# IR_Transmitter.net
KiCad netlist of a schematic drawn in Altium Designer
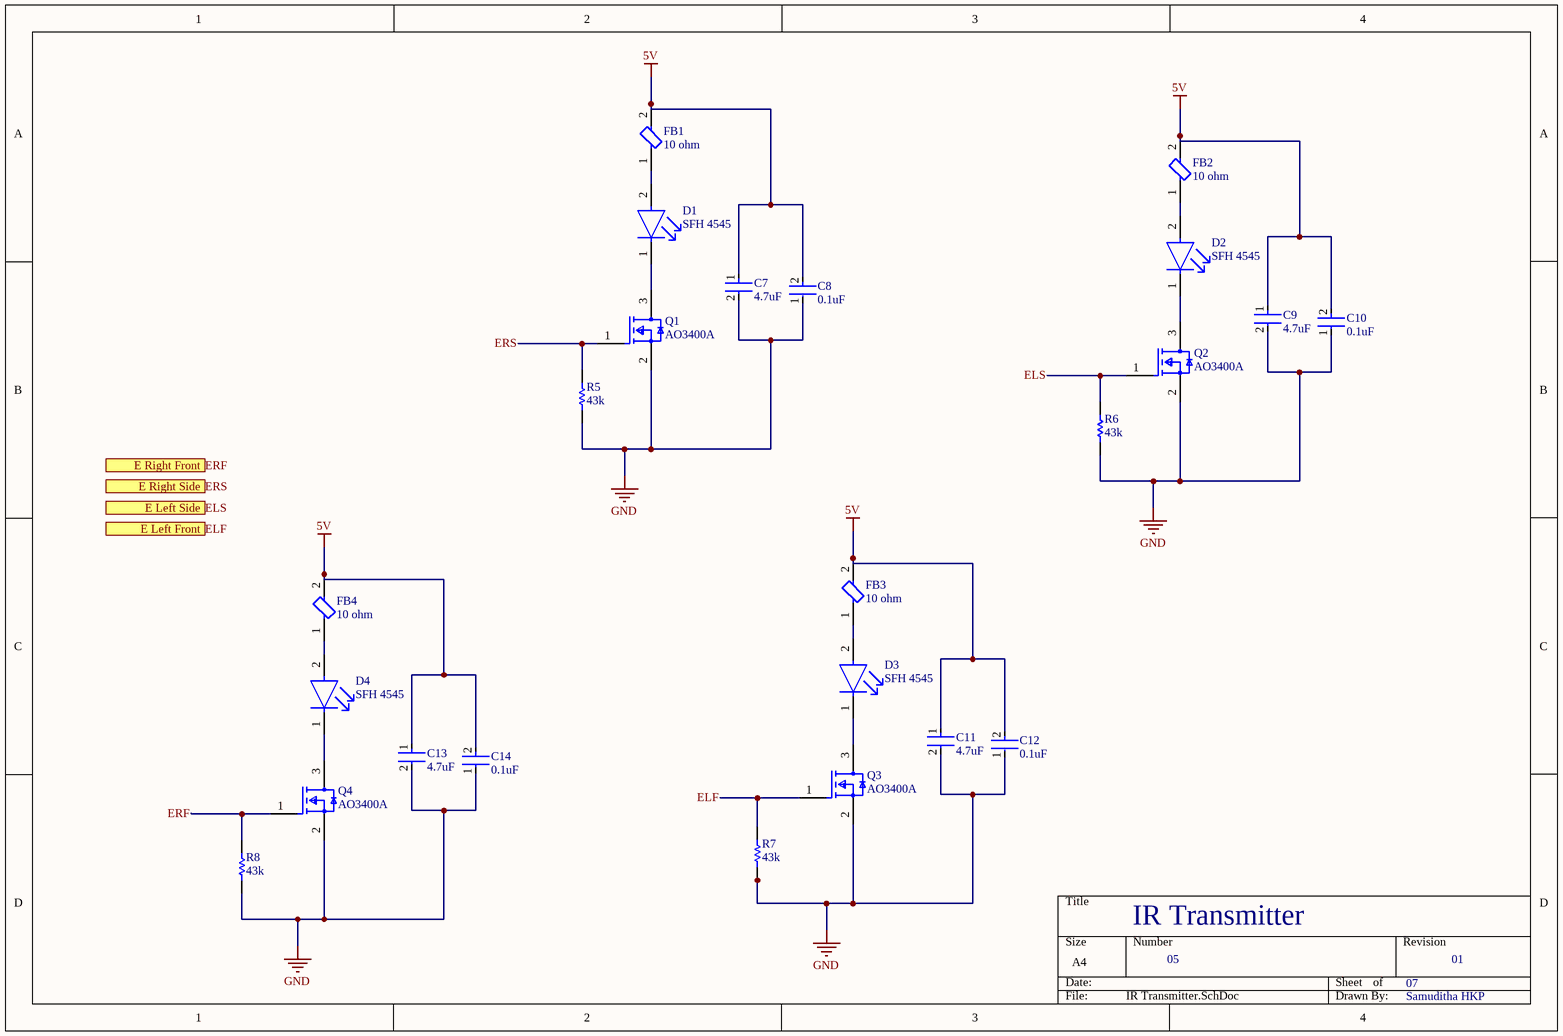
[diagram p0: IR Transmitter.SchDoc]

(export (version "E")
  (design (tool "Eeschema 10.0.6"))
  (components
    (comp (ref "C7")
      (value "4.7uF")
      (footprint "FP-GRM155-0_1-IPC_B")
      (description "Chip Multilayer Ceramic Capacitors for General Purpose, 0402, 4.7uF, X5R, 15%, 20%, 6.3V")
      (fields (field (name "VOLTAGE") "6.3V") (field (name "TOLERANCE") "20%"))
      (libsource (lib "Altium Content Vault") (part "11868f565c42a9108669ba33697ecf6"))
    )
    (comp (ref "C8")
      (value "0.1uF")
      (footprint "FP-GRM15-MFG")
      (description "CAP CER 0.1UF 16V X7R 0402")
      (fields (field (name "MANUFACTURER PART NUMBER") "GRM155R71C104KA88D") (field (name "TOLERANCE") "10%"))
      (libsource (lib "Altium Content Vault") (part "236180d848d6139a670b325ea6854c9"))
    )
    (comp (ref "C9")
      (value "4.7uF")
      (footprint "FP-GRM155-0_1-IPC_B")
      (description "Chip Multilayer Ceramic Capacitors for General Purpose, 0402, 4.7uF, X5R, 15%, 20%, 6.3V")
      (fields (field (name "VOLTAGE") "6.3V") (field (name "TOLERANCE") "20%"))
      (libsource (lib "Altium Content Vault") (part "11868f565c42a9108669ba33697ecf6"))
    )
    (comp (ref "C10")
      (value "0.1uF")
      (footprint "FP-GRM15-MFG")
      (description "CAP CER 0.1UF 16V X7R 0402")
      (fields (field (name "MANUFACTURER PART NUMBER") "GRM155R71C104KA88D") (field (name "TOLERANCE") "10%"))
      (libsource (lib "Altium Content Vault") (part "236180d848d6139a670b325ea6854c9"))
    )
    (comp (ref "C11")
      (value "4.7uF")
      (footprint "FP-GRM155-0_1-IPC_B")
      (description "Chip Multilayer Ceramic Capacitors for General Purpose, 0402, 4.7uF, X5R, 15%, 20%, 6.3V")
      (fields (field (name "VOLTAGE") "6.3V") (field (name "TOLERANCE") "20%"))
      (libsource (lib "Altium Content Vault") (part "11868f565c42a9108669ba33697ecf6"))
    )
    (comp (ref "C12")
      (value "0.1uF")
      (footprint "FP-GRM15-MFG")
      (description "CAP CER 0.1UF 16V X7R 0402")
      (fields (field (name "MANUFACTURER PART NUMBER") "GRM155R71C104KA88D") (field (name "TOLERANCE") "10%"))
      (libsource (lib "Altium Content Vault") (part "236180d848d6139a670b325ea6854c9"))
    )
    (comp (ref "C13")
      (value "4.7uF")
      (footprint "FP-GRM155-0_1-IPC_B")
      (description "Chip Multilayer Ceramic Capacitors for General Purpose, 0402, 4.7uF, X5R, 15%, 20%, 6.3V")
      (fields (field (name "VOLTAGE") "6.3V") (field (name "TOLERANCE") "20%"))
      (libsource (lib "Altium Content Vault") (part "11868f565c42a9108669ba33697ecf6"))
    )
    (comp (ref "C14")
      (value "0.1uF")
      (footprint "FP-GRM15-MFG")
      (description "CAP CER 0.1UF 16V X7R 0402")
      (fields (field (name "MANUFACTURER PART NUMBER") "GRM155R71C104KA88D") (field (name "TOLERANCE") "10%"))
      (libsource (lib "Altium Content Vault") (part "236180d848d6139a670b325ea6854c9"))
    )
    (comp (ref "D1")
      (value "SFH 4545")
      (footprint "FP-SFH_4556-MFG")
      (description "EMITTER IR 860NM 100MA RADIAL")
      (fields
        (field (name "OCTOPART") "https://octopart.com/sfh+4556-osram+opto-31094094")
        (field (name "MANUFACTURER PART NUMBER") "SFH 4556")
      )
      (libsource (lib "Altium Content Vault") (part "8706943c75ba83719d021d2fdc84c58"))
    )
    (comp (ref "D2")
      (value "SFH 4545")
      (footprint "FP-SFH_4556-MFG")
      (description "EMITTER IR 860NM 100MA RADIAL")
      (fields
        (field (name "OCTOPART") "https://octopart.com/sfh+4556-osram+opto-31094094")
        (field (name "MANUFACTURER PART NUMBER") "SFH 4556")
      )
      (libsource (lib "Altium Content Vault") (part "8706943c75ba83719d021d2fdc84c58"))
    )
    (comp (ref "D3")
      (value "SFH 4545")
      (footprint "FP-SFH_4556-MFG")
      (description "EMITTER IR 860NM 100MA RADIAL")
      (fields
        (field (name "OCTOPART") "https://octopart.com/sfh+4556-osram+opto-31094094")
        (field (name "MANUFACTURER PART NUMBER") "SFH 4556")
      )
      (libsource (lib "Altium Content Vault") (part "8706943c75ba83719d021d2fdc84c58"))
    )
    (comp (ref "D4")
      (value "SFH 4545")
      (footprint "FP-SFH_4556-MFG")
      (description "EMITTER IR 860NM 100MA RADIAL")
      (fields
        (field (name "OCTOPART") "https://octopart.com/sfh+4556-osram+opto-31094094")
        (field (name "MANUFACTURER PART NUMBER") "SFH 4556")
      )
      (libsource (lib "Altium Content Vault") (part "8706943c75ba83719d021d2fdc84c58"))
    )
    (comp (ref "FB1")
      (value "10 ohm")
      (footprint "FP-BLM15-0_05-MFG")
      (description "Chip Ferrite Bead, 0402, 10Ω @ 100MHz, 0.1Ω, 25%, 300mA")
      (fields (field (name "TOLERANCE") "25%"))
      (libsource (lib "Altium Content Vault") (part "5f30dd21d616792df468990f7003faa"))
    )
    (comp (ref "FB2")
      (value "10 ohm")
      (footprint "FP-BLM15-0_05-MFG")
      (description "Chip Ferrite Bead, 0402, 10Ω @ 100MHz, 0.1Ω, 25%, 300mA")
      (fields (field (name "TOLERANCE") "25%"))
      (libsource (lib "Altium Content Vault") (part "5f30dd21d616792df468990f7003faa"))
    )
    (comp (ref "FB3")
      (value "10 ohm")
      (footprint "FP-BLM15-0_05-MFG")
      (description "Chip Ferrite Bead, 0402, 10Ω @ 100MHz, 0.1Ω, 25%, 300mA")
      (fields (field (name "TOLERANCE") "25%"))
      (libsource (lib "Altium Content Vault") (part "5f30dd21d616792df468990f7003faa"))
    )
    (comp (ref "FB4")
      (value "10 ohm")
      (footprint "FP-BLM15-0_05-MFG")
      (description "Chip Ferrite Bead, 0402, 10Ω @ 100MHz, 0.1Ω, 25%, 300mA")
      (fields (field (name "TOLERANCE") "25%"))
      (libsource (lib "Altium Content Vault") (part "5f30dd21d616792df468990f7003faa"))
    )
    (comp (ref "Q1")
      (value "AO3400A")
      (footprint "FP-SOT23-MFG")
      (description "MOSFET N-CH 30V 5.7A SOT23")
      (libsource (lib "Altium Content Vault") (part "0a9ea7c96deaaede766a5b531c28de0"))
    )
    (comp (ref "Q2")
      (value "AO3400A")
      (footprint "FP-SOT23-MFG")
      (description "MOSFET N-CH 30V 5.7A SOT23")
      (libsource (lib "Altium Content Vault") (part "0a9ea7c96deaaede766a5b531c28de0"))
    )
    (comp (ref "Q3")
      (value "AO3400A")
      (footprint "FP-SOT23-MFG")
      (description "MOSFET N-CH 30V 5.7A SOT23")
      (libsource (lib "Altium Content Vault") (part "0a9ea7c96deaaede766a5b531c28de0"))
    )
    (comp (ref "Q4")
      (value "AO3400A")
      (footprint "FP-SOT23-MFG")
      (description "MOSFET N-CH 30V 5.7A SOT23")
      (libsource (lib "Altium Content Vault") (part "0a9ea7c96deaaede766a5b531c28de0"))
    )
    (comp (ref "R5")
      (value "43k")
      (footprint "RESC1005X40X25NL05T05")
      (fields (field (name "PART NUMBER") "CRCW040243K0FKED") (field (name "MANUFACTURER") "Vishay Dale"))
      (libsource (lib "Altium Content Vault") (part "RES"))
    )
    (comp (ref "R6")
      (value "43k")
      (footprint "RESC1005X40X25NL05T05")
      (fields (field (name "PART NUMBER") "CRCW040243K0FKED") (field (name "MANUFACTURER") "Vishay Dale"))
      (libsource (lib "Altium Content Vault") (part "RES"))
    )
    (comp (ref "R7")
      (value "43k")
      (footprint "RESC1005X40X25NL05T05")
      (fields (field (name "PART NUMBER") "CRCW040243K0FKED") (field (name "MANUFACTURER") "Vishay Dale"))
      (libsource (lib "Altium Content Vault") (part "RES"))
    )
    (comp (ref "R8")
      (value "43k")
      (footprint "RESC1005X40X25NL05T05")
      (fields (field (name "PART NUMBER") "CRCW040243K0FKED") (field (name "MANUFACTURER") "Vishay Dale"))
      (libsource (lib "Altium Content Vault") (part "RES"))
    )
  )
  (nets
    (net (code "1") (name "/ELF") (class "Default")
      (node (ref "Q3") (pin "1") (pinfunction "G_1") (pintype "passive"))
      (node (ref "R7") (pin "2") (pinfunction "2_2") (pintype "passive"))
    )
    (net (code "2") (name "/ELS") (class "Default")
      (node (ref "Q2") (pin "1") (pinfunction "G_1") (pintype "passive"))
      (node (ref "R6") (pin "2") (pinfunction "2_2") (pintype "passive"))
    )
    (net (code "3") (name "/ERF") (class "Default")
      (node (ref "Q4") (pin "1") (pinfunction "G_1") (pintype "passive"))
      (node (ref "R8") (pin "2") (pinfunction "2_2") (pintype "passive"))
    )
    (net (code "4") (name "/ERS") (class "Default")
      (node (ref "Q1") (pin "1") (pinfunction "G_1") (pintype "passive"))
      (node (ref "R5") (pin "2") (pinfunction "2_2") (pintype "passive"))
    )
    (net (code "5") (name "5V") (class "Default")
      (node (ref "C10") (pin "2") (pinfunction "2_2") (pintype "passive"))
      (node (ref "C11") (pin "1") (pinfunction "1_1") (pintype "passive"))
      (node (ref "C12") (pin "2") (pinfunction "2_2") (pintype "passive"))
      (node (ref "C13") (pin "1") (pinfunction "1_1") (pintype "passive"))
      (node (ref "C14") (pin "2") (pinfunction "2_2") (pintype "passive"))
      (node (ref "C7") (pin "1") (pinfunction "1_1") (pintype "passive"))
      (node (ref "C8") (pin "2") (pinfunction "2_2") (pintype "passive"))
      (node (ref "C9") (pin "1") (pinfunction "1_1") (pintype "passive"))
      (node (ref "FB1") (pin "2") (pinfunction "2_2") (pintype "passive"))
      (node (ref "FB2") (pin "2") (pinfunction "2_2") (pintype "passive"))
      (node (ref "FB3") (pin "2") (pinfunction "2_2") (pintype "passive"))
      (node (ref "FB4") (pin "2") (pinfunction "2_2") (pintype "passive"))
    )
    (net (code "6") (name "GND") (class "Default")
      (node (ref "C10") (pin "1") (pinfunction "1_1") (pintype "passive"))
      (node (ref "C11") (pin "2") (pinfunction "2_2") (pintype "passive"))
      (node (ref "C12") (pin "1") (pinfunction "1_1") (pintype "passive"))
      (node (ref "C13") (pin "2") (pinfunction "2_2") (pintype "passive"))
      (node (ref "C14") (pin "1") (pinfunction "1_1") (pintype "passive"))
      (node (ref "C7") (pin "2") (pinfunction "2_2") (pintype "passive"))
      (node (ref "C8") (pin "1") (pinfunction "1_1") (pintype "passive"))
      (node (ref "C9") (pin "2") (pinfunction "2_2") (pintype "passive"))
      (node (ref "Q1") (pin "2") (pinfunction "S_2") (pintype "passive"))
      (node (ref "Q2") (pin "2") (pinfunction "S_2") (pintype "passive"))
      (node (ref "Q3") (pin "2") (pinfunction "S_2") (pintype "passive"))
      (node (ref "Q4") (pin "2") (pinfunction "S_2") (pintype "passive"))
      (node (ref "R5") (pin "1") (pinfunction "1_1") (pintype "passive"))
      (node (ref "R6") (pin "1") (pinfunction "1_1") (pintype "passive"))
      (node (ref "R7") (pin "1") (pinfunction "1_1") (pintype "passive"))
      (node (ref "R8") (pin "1") (pinfunction "1_1") (pintype "passive"))
    )
    (net (code "7") (name "Net-(D1-A)") (class "Default")
      (node (ref "D1") (pin "2") (pinfunction "A_2") (pintype "passive"))
      (node (ref "FB1") (pin "1") (pinfunction "1_1") (pintype "passive"))
    )
    (net (code "8") (name "Net-(D1-C)") (class "Default")
      (node (ref "D1") (pin "1") (pinfunction "C_1") (pintype "passive"))
      (node (ref "Q1") (pin "3") (pinfunction "D_3") (pintype "passive"))
    )
    (net (code "9") (name "Net-(D2-A)") (class "Default")
      (node (ref "D2") (pin "2") (pinfunction "A_2") (pintype "passive"))
      (node (ref "FB2") (pin "1") (pinfunction "1_1") (pintype "passive"))
    )
    (net (code "10") (name "Net-(D2-C)") (class "Default")
      (node (ref "D2") (pin "1") (pinfunction "C_1") (pintype "passive"))
      (node (ref "Q2") (pin "3") (pinfunction "D_3") (pintype "passive"))
    )
    (net (code "11") (name "Net-(D3-A)") (class "Default")
      (node (ref "D3") (pin "2") (pinfunction "A_2") (pintype "passive"))
      (node (ref "FB3") (pin "1") (pinfunction "1_1") (pintype "passive"))
    )
    (net (code "12") (name "Net-(D3-C)") (class "Default")
      (node (ref "D3") (pin "1") (pinfunction "C_1") (pintype "passive"))
      (node (ref "Q3") (pin "3") (pinfunction "D_3") (pintype "passive"))
    )
    (net (code "13") (name "Net-(D4-A)") (class "Default")
      (node (ref "D4") (pin "2") (pinfunction "A_2") (pintype "passive"))
      (node (ref "FB4") (pin "1") (pinfunction "1_1") (pintype "passive"))
    )
    (net (code "14") (name "Net-(D4-C)") (class "Default")
      (node (ref "D4") (pin "1") (pinfunction "C_1") (pintype "passive"))
      (node (ref "Q4") (pin "3") (pinfunction "D_3") (pintype "passive"))
    )
  )
)
